# v3_1.net
KiCad netlist of a schematic drawn in EAGLE
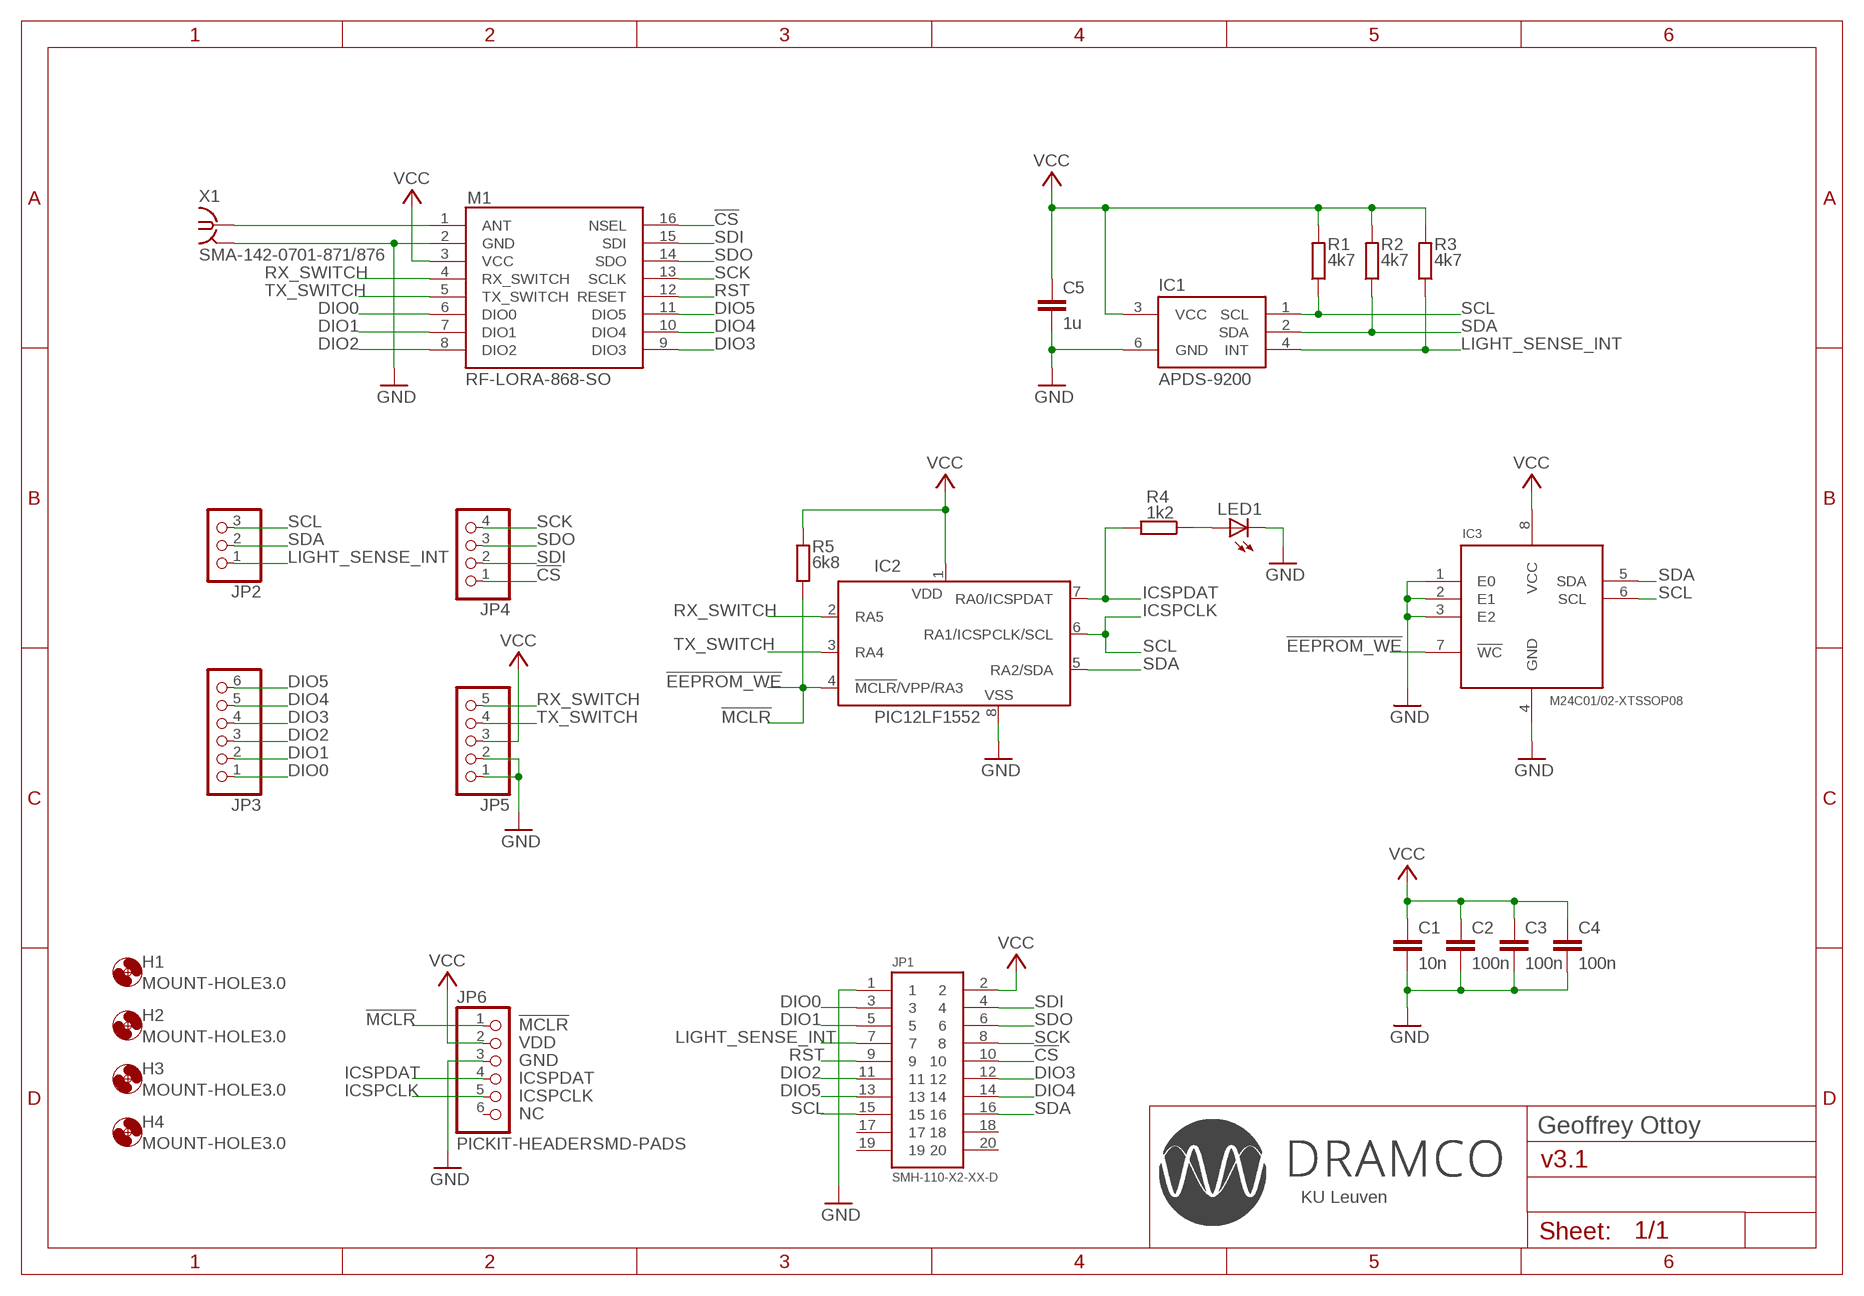
[diagram p0: schematic, sheet 1]

(export (version "E")
  (design (tool "Eeschema 10.0.6"))
  (components
    (comp (ref "C1")
      (value "10n")
      (footprint "eagle-import:C0805K")
      (libsource (lib "eagle-import") (part "C-EUC0805K"))
    )
    (comp (ref "C2")
      (value "100n")
      (footprint "eagle-import:C0805K")
      (libsource (lib "eagle-import") (part "C-EUC0805K"))
    )
    (comp (ref "C3")
      (value "100n")
      (footprint "eagle-import:C0805K")
      (libsource (lib "eagle-import") (part "C-EUC0805K"))
    )
    (comp (ref "C4")
      (value "100n")
      (footprint "eagle-import:C0805K")
      (libsource (lib "eagle-import") (part "C-EUC0805K"))
    )
    (comp (ref "C5")
      (value "1u")
      (footprint "eagle-import:C0805K")
      (libsource (lib "eagle-import") (part "C-EUC0805K"))
    )
    (comp (ref "H1")
      (value "MOUNT-HOLE3.0")
      (footprint "eagle-import:3,0")
      (libsource (lib "eagle-import") (part "MOUNT-HOLE3.0"))
    )
    (comp (ref "H2")
      (value "MOUNT-HOLE3.0")
      (footprint "eagle-import:3,0")
      (libsource (lib "eagle-import") (part "MOUNT-HOLE3.0"))
    )
    (comp (ref "H3")
      (value "MOUNT-HOLE3.0")
      (footprint "eagle-import:3,0")
      (libsource (lib "eagle-import") (part "MOUNT-HOLE3.0"))
    )
    (comp (ref "H4")
      (value "MOUNT-HOLE3.0")
      (footprint "eagle-import:3,0")
      (libsource (lib "eagle-import") (part "MOUNT-HOLE3.0"))
    )
    (comp (ref "IC1")
      (value "APDS-9200")
      (footprint "eagle-import:APDS-9200")
      (libsource (lib "eagle-import") (part "APDS-9200"))
    )
    (comp (ref "IC2")
      (value "PIC12LF1552")
      (footprint "eagle-import:MSOP8")
      (libsource (lib "eagle-import") (part "PIC12LF1552"))
    )
    (comp (ref "IC3")
      (value "M24C01/02-XTSSOP08")
      (footprint "eagle-import:TSSOP08")
      (libsource (lib "eagle-import") (part "M24C01/02-XTSSOP08"))
    )
    (comp (ref "JP1")
      (value "SMH-110-X2-XX-D")
      (footprint "eagle-import:SMH-110-X2-XX-D")
      (libsource (lib "eagle-import") (part "SMH-110-X2-XX-D"))
    )
    (comp (ref "JP2")
      (value "PINHD-1X3")
      (footprint "eagle-import:1X03")
      (libsource (lib "eagle-import") (part "PINHD-1X3"))
    )
    (comp (ref "JP3")
      (value "PINHD-1X6")
      (footprint "eagle-import:1X06")
      (libsource (lib "eagle-import") (part "PINHD-1X6"))
    )
    (comp (ref "JP4")
      (value "PINHD-1X4")
      (footprint "eagle-import:1X04")
      (libsource (lib "eagle-import") (part "PINHD-1X4"))
    )
    (comp (ref "JP5")
      (value "PINHD-1X5")
      (footprint "eagle-import:1X05")
      (libsource (lib "eagle-import") (part "PINHD-1X5"))
    )
    (comp (ref "JP6")
      (value "PICKIT-HEADERSMD-PADS")
      (footprint "eagle-import:1X06_SMD")
      (libsource (lib "eagle-import") (part "PICKIT-HEADERSMD-PADS"))
    )
    (comp (ref "LED1")
      (value "LEDCHIP-LED0805")
      (footprint "eagle-import:CHIP-LED0805")
      (libsource (lib "eagle-import") (part "LEDCHIP-LED0805"))
    )
    (comp (ref "M1")
      (value "RF-LORA-868-SO")
      (footprint "eagle-import:RF-LORA-868-SO")
      (libsource (lib "eagle-import") (part "RF-LORA-868-SO"))
    )
    (comp (ref "R1")
      (value "4k7")
      (footprint "eagle-import:M0805")
      (libsource (lib "eagle-import") (part "R-EU_M0805"))
    )
    (comp (ref "R2")
      (value "4k7")
      (footprint "eagle-import:M0805")
      (libsource (lib "eagle-import") (part "R-EU_M0805"))
    )
    (comp (ref "R3")
      (value "4k7")
      (footprint "eagle-import:M0805")
      (libsource (lib "eagle-import") (part "R-EU_M0805"))
    )
    (comp (ref "R4")
      (value "1k2")
      (footprint "eagle-import:M0805")
      (libsource (lib "eagle-import") (part "R-EU_M0805"))
    )
    (comp (ref "R5")
      (value "6k8")
      (footprint "eagle-import:M0805")
      (libsource (lib "eagle-import") (part "R-EU_M0805"))
    )
    (comp (ref "X1")
      (value "SMA-142-0701-871/876")
      (footprint "eagle-import:J502-ND-142-0701-871_876")
      (fields (field (name "MF") "JOHNSON COMPONENTS") (field (name "MPN") "142-0701-871"))
      (libsource (lib "eagle-import") (part "SMA-142-0701-871/876"))
    )
  )
  (nets
    (net (code "1") (name "/DIO0") (class "Default")
      (node (ref "JP1") (pin "3") (pinfunction "3_3") (pintype "bidirectional"))
      (node (ref "JP3") (pin "1") (pinfunction "1_1") (pintype "passive"))
      (node (ref "M1") (pin "6") (pinfunction "DIO0_6") (pintype "bidirectional"))
    )
    (net (code "2") (name "/DIO1") (class "Default")
      (node (ref "JP1") (pin "5") (pinfunction "5_5") (pintype "bidirectional"))
      (node (ref "JP3") (pin "2") (pinfunction "2_2") (pintype "passive"))
      (node (ref "M1") (pin "7") (pinfunction "DIO1_7") (pintype "bidirectional"))
    )
    (net (code "3") (name "/DIO2") (class "Default")
      (node (ref "JP1") (pin "11") (pinfunction "11_11") (pintype "bidirectional"))
      (node (ref "JP3") (pin "3") (pinfunction "3_3") (pintype "passive"))
      (node (ref "M1") (pin "8") (pinfunction "DIO2_8") (pintype "bidirectional"))
    )
    (net (code "4") (name "/DIO3") (class "Default")
      (node (ref "JP1") (pin "12") (pinfunction "12_12") (pintype "bidirectional"))
      (node (ref "JP3") (pin "4") (pinfunction "4_4") (pintype "passive"))
      (node (ref "M1") (pin "9") (pinfunction "DIO3_9") (pintype "bidirectional"))
    )
    (net (code "5") (name "/DIO4") (class "Default")
      (node (ref "JP1") (pin "14") (pinfunction "14_14") (pintype "bidirectional"))
      (node (ref "JP3") (pin "5") (pinfunction "5_5") (pintype "passive"))
      (node (ref "M1") (pin "10") (pinfunction "DIO4_10") (pintype "bidirectional"))
    )
    (net (code "6") (name "/DIO5") (class "Default")
      (node (ref "JP1") (pin "13") (pinfunction "13_13") (pintype "bidirectional"))
      (node (ref "JP3") (pin "6") (pinfunction "6_6") (pintype "passive"))
      (node (ref "M1") (pin "11") (pinfunction "DIO5_11") (pintype "bidirectional"))
    )
    (net (code "7") (name "/ICSPDAT") (class "Default")
      (node (ref "IC2") (pin "7") (pinfunction "RA0/ICSPDAT_7") (pintype "bidirectional"))
      (node (ref "JP6") (pin "4") (pinfunction "4_4") (pintype "passive"))
      (node (ref "R4") (pin "2") (pinfunction "2_2") (pintype "passive"))
    )
    (net (code "8") (name "/LIGHT_SENSE_INT") (class "Default")
      (node (ref "IC1") (pin "4") (pinfunction "INT_4") (pintype "bidirectional"))
      (node (ref "JP1") (pin "7") (pinfunction "7_7") (pintype "bidirectional"))
      (node (ref "JP2") (pin "1") (pinfunction "1_1") (pintype "passive"))
      (node (ref "R3") (pin "1") (pinfunction "1_1") (pintype "passive"))
    )
    (net (code "9") (name "/RST") (class "Default")
      (node (ref "JP1") (pin "9") (pinfunction "9_9") (pintype "bidirectional"))
      (node (ref "M1") (pin "12") (pinfunction "RESET_12") (pintype "bidirectional"))
    )
    (net (code "10") (name "/RX_SWITCH") (class "Default")
      (node (ref "IC2") (pin "2") (pinfunction "RA5_2") (pintype "bidirectional"))
      (node (ref "JP5") (pin "5") (pinfunction "5_5") (pintype "passive"))
      (node (ref "M1") (pin "4") (pinfunction "RX_SWITCH_4") (pintype "bidirectional"))
    )
    (net (code "11") (name "/SCK") (class "Default")
      (node (ref "JP1") (pin "8") (pinfunction "8_8") (pintype "bidirectional"))
      (node (ref "JP4") (pin "4") (pinfunction "4_4") (pintype "passive"))
      (node (ref "M1") (pin "13") (pinfunction "SCLK_13") (pintype "bidirectional"))
    )
    (net (code "12") (name "/SCL") (class "Default")
      (node (ref "IC1") (pin "1") (pinfunction "SCL_1") (pintype "bidirectional"))
      (node (ref "IC2") (pin "6") (pinfunction "RA1/ICSPCLK/SCL_6") (pintype "bidirectional"))
      (node (ref "IC3") (pin "6") (pinfunction "SCL_6") (pintype "bidirectional"))
      (node (ref "JP1") (pin "15") (pinfunction "15_15") (pintype "bidirectional"))
      (node (ref "JP2") (pin "3") (pinfunction "3_3") (pintype "passive"))
      (node (ref "JP6") (pin "5") (pinfunction "5_5") (pintype "passive"))
      (node (ref "R1") (pin "1") (pinfunction "1_1") (pintype "passive"))
    )
    (net (code "13") (name "/SDA") (class "Default")
      (node (ref "IC1") (pin "2") (pinfunction "SDA_2") (pintype "bidirectional"))
      (node (ref "IC2") (pin "5") (pinfunction "RA2/SDA_5") (pintype "bidirectional"))
      (node (ref "IC3") (pin "5") (pinfunction "SDA_5") (pintype "bidirectional"))
      (node (ref "JP1") (pin "16") (pinfunction "16_16") (pintype "bidirectional"))
      (node (ref "JP2") (pin "2") (pinfunction "2_2") (pintype "passive"))
      (node (ref "R2") (pin "1") (pinfunction "1_1") (pintype "passive"))
    )
    (net (code "14") (name "/SDI") (class "Default")
      (node (ref "JP1") (pin "4") (pinfunction "4_4") (pintype "bidirectional"))
      (node (ref "JP4") (pin "2") (pinfunction "2_2") (pintype "passive"))
      (node (ref "M1") (pin "15") (pinfunction "SDI_15") (pintype "bidirectional"))
    )
    (net (code "15") (name "/SDO") (class "Default")
      (node (ref "JP1") (pin "6") (pinfunction "6_6") (pintype "bidirectional"))
      (node (ref "JP4") (pin "3") (pinfunction "3_3") (pintype "passive"))
      (node (ref "M1") (pin "14") (pinfunction "SDO_14") (pintype "bidirectional"))
    )
    (net (code "16") (name "/TX_SWITCH") (class "Default")
      (node (ref "IC2") (pin "3") (pinfunction "RA4_3") (pintype "bidirectional"))
      (node (ref "JP5") (pin "4") (pinfunction "4_4") (pintype "passive"))
      (node (ref "M1") (pin "5") (pinfunction "TX_SWITCH_5") (pintype "bidirectional"))
    )
    (net (code "17") (name "/~{CS}") (class "Default")
      (node (ref "JP1") (pin "10") (pinfunction "10_10") (pintype "bidirectional"))
      (node (ref "JP4") (pin "1") (pinfunction "1_1") (pintype "passive"))
      (node (ref "M1") (pin "16") (pinfunction "NSEL_16") (pintype "bidirectional"))
    )
    (net (code "18") (name "/~{MCLR}") (class "Default")
      (node (ref "IC2") (pin "4") (pinfunction "~{MCLR}/VPP/RA3_4") (pintype "input"))
      (node (ref "IC3") (pin "7") (pinfunction "~{WC}_7") (pintype "bidirectional"))
      (node (ref "JP6") (pin "1") (pinfunction "1_1") (pintype "passive"))
      (node (ref "R5") (pin "1") (pinfunction "1_1") (pintype "passive"))
    )
    (net (code "19") (name "GND") (class "Default")
      (node (ref "C1") (pin "2") (pinfunction "2_2") (pintype "passive"))
      (node (ref "C2") (pin "2") (pinfunction "2_2") (pintype "passive"))
      (node (ref "C3") (pin "2") (pinfunction "2_2") (pintype "passive"))
      (node (ref "C4") (pin "2") (pinfunction "2_2") (pintype "passive"))
      (node (ref "C5") (pin "2") (pinfunction "2_2") (pintype "passive"))
      (node (ref "IC1") (pin "6") (pinfunction "GND_6") (pintype "bidirectional"))
      (node (ref "IC2") (pin "8") (pinfunction "VSS_8") (pintype "power_in"))
      (node (ref "IC3") (pin "1") (pinfunction "E0_1") (pintype "bidirectional"))
      (node (ref "IC3") (pin "2") (pinfunction "E1_2") (pintype "bidirectional"))
      (node (ref "IC3") (pin "3") (pinfunction "E2_3") (pintype "bidirectional"))
      (node (ref "IC3") (pin "4") (pinfunction "GND_4") (pintype "bidirectional"))
      (node (ref "JP1") (pin "1") (pinfunction "1_1") (pintype "bidirectional"))
      (node (ref "JP5") (pin "1") (pinfunction "1_1") (pintype "passive"))
      (node (ref "JP5") (pin "2") (pinfunction "2_2") (pintype "passive"))
      (node (ref "JP6") (pin "3") (pinfunction "3_3") (pintype "passive"))
      (node (ref "LED1") (pin "C") (pinfunction "C_C") (pintype "passive"))
      (node (ref "M1") (pin "2") (pinfunction "GND_2") (pintype "bidirectional"))
      (node (ref "X1") (pin "G@1") (pinfunction "2_G@1") (pintype "passive"))
      (node (ref "X1") (pin "G@2") (pinfunction "2_G@2") (pintype "passive"))
      (node (ref "X1") (pin "G@3") (pinfunction "2_G@3") (pintype "passive"))
      (node (ref "X1") (pin "G@4") (pinfunction "2_G@4") (pintype "passive"))
    )
    (net (code "20") (name "Net-(LED1-PadA)") (class "Default")
      (node (ref "LED1") (pin "A") (pinfunction "A_A") (pintype "passive"))
      (node (ref "R4") (pin "1") (pinfunction "1_1") (pintype "passive"))
    )
    (net (code "21") (name "Net-(M1-ANT)") (class "Default")
      (node (ref "M1") (pin "1") (pinfunction "ANT_1") (pintype "bidirectional"))
      (node (ref "X1") (pin "1") (pinfunction "1_1") (pintype "passive"))
    )
    (net (code "22") (name "VCC") (class "Default")
      (node (ref "C1") (pin "1") (pinfunction "1_1") (pintype "passive"))
      (node (ref "C2") (pin "1") (pinfunction "1_1") (pintype "passive"))
      (node (ref "C3") (pin "1") (pinfunction "1_1") (pintype "passive"))
      (node (ref "C4") (pin "1") (pinfunction "1_1") (pintype "passive"))
      (node (ref "C5") (pin "1") (pinfunction "1_1") (pintype "passive"))
      (node (ref "IC1") (pin "3") (pinfunction "VCC_3") (pintype "bidirectional"))
      (node (ref "IC2") (pin "1") (pinfunction "VDD_1") (pintype "power_in"))
      (node (ref "IC3") (pin "8") (pinfunction "VCC_8") (pintype "bidirectional"))
      (node (ref "JP1") (pin "2") (pinfunction "2_2") (pintype "bidirectional"))
      (node (ref "JP5") (pin "3") (pinfunction "3_3") (pintype "passive"))
      (node (ref "JP6") (pin "2") (pinfunction "2_2") (pintype "passive"))
      (node (ref "M1") (pin "3") (pinfunction "VCC_3") (pintype "bidirectional"))
      (node (ref "R1") (pin "2") (pinfunction "2_2") (pintype "passive"))
      (node (ref "R2") (pin "2") (pinfunction "2_2") (pintype "passive"))
      (node (ref "R3") (pin "2") (pinfunction "2_2") (pintype "passive"))
      (node (ref "R5") (pin "2") (pinfunction "2_2") (pintype "passive"))
    )
    (net (code "23") (name "unconnected-(JP1-Pad17)") (class "Default")
      (node (ref "JP1") (pin "17") (pinfunction "17_17") (pintype "bidirectional"))
    )
    (net (code "24") (name "unconnected-(JP1-Pad18)") (class "Default")
      (node (ref "JP1") (pin "18") (pinfunction "18_18") (pintype "bidirectional"))
    )
    (net (code "25") (name "unconnected-(JP1-Pad19)") (class "Default")
      (node (ref "JP1") (pin "19") (pinfunction "19_19") (pintype "bidirectional"))
    )
    (net (code "26") (name "unconnected-(JP1-Pad20)") (class "Default")
      (node (ref "JP1") (pin "20") (pinfunction "20_20") (pintype "bidirectional"))
    )
    (net (code "27") (name "unconnected-(JP6-Pad6)") (class "Default")
      (node (ref "JP6") (pin "6") (pinfunction "6_6") (pintype "passive"))
    )
  )
)
